# Schematic.net
KiCad netlist of a schematic drawn in EAGLE
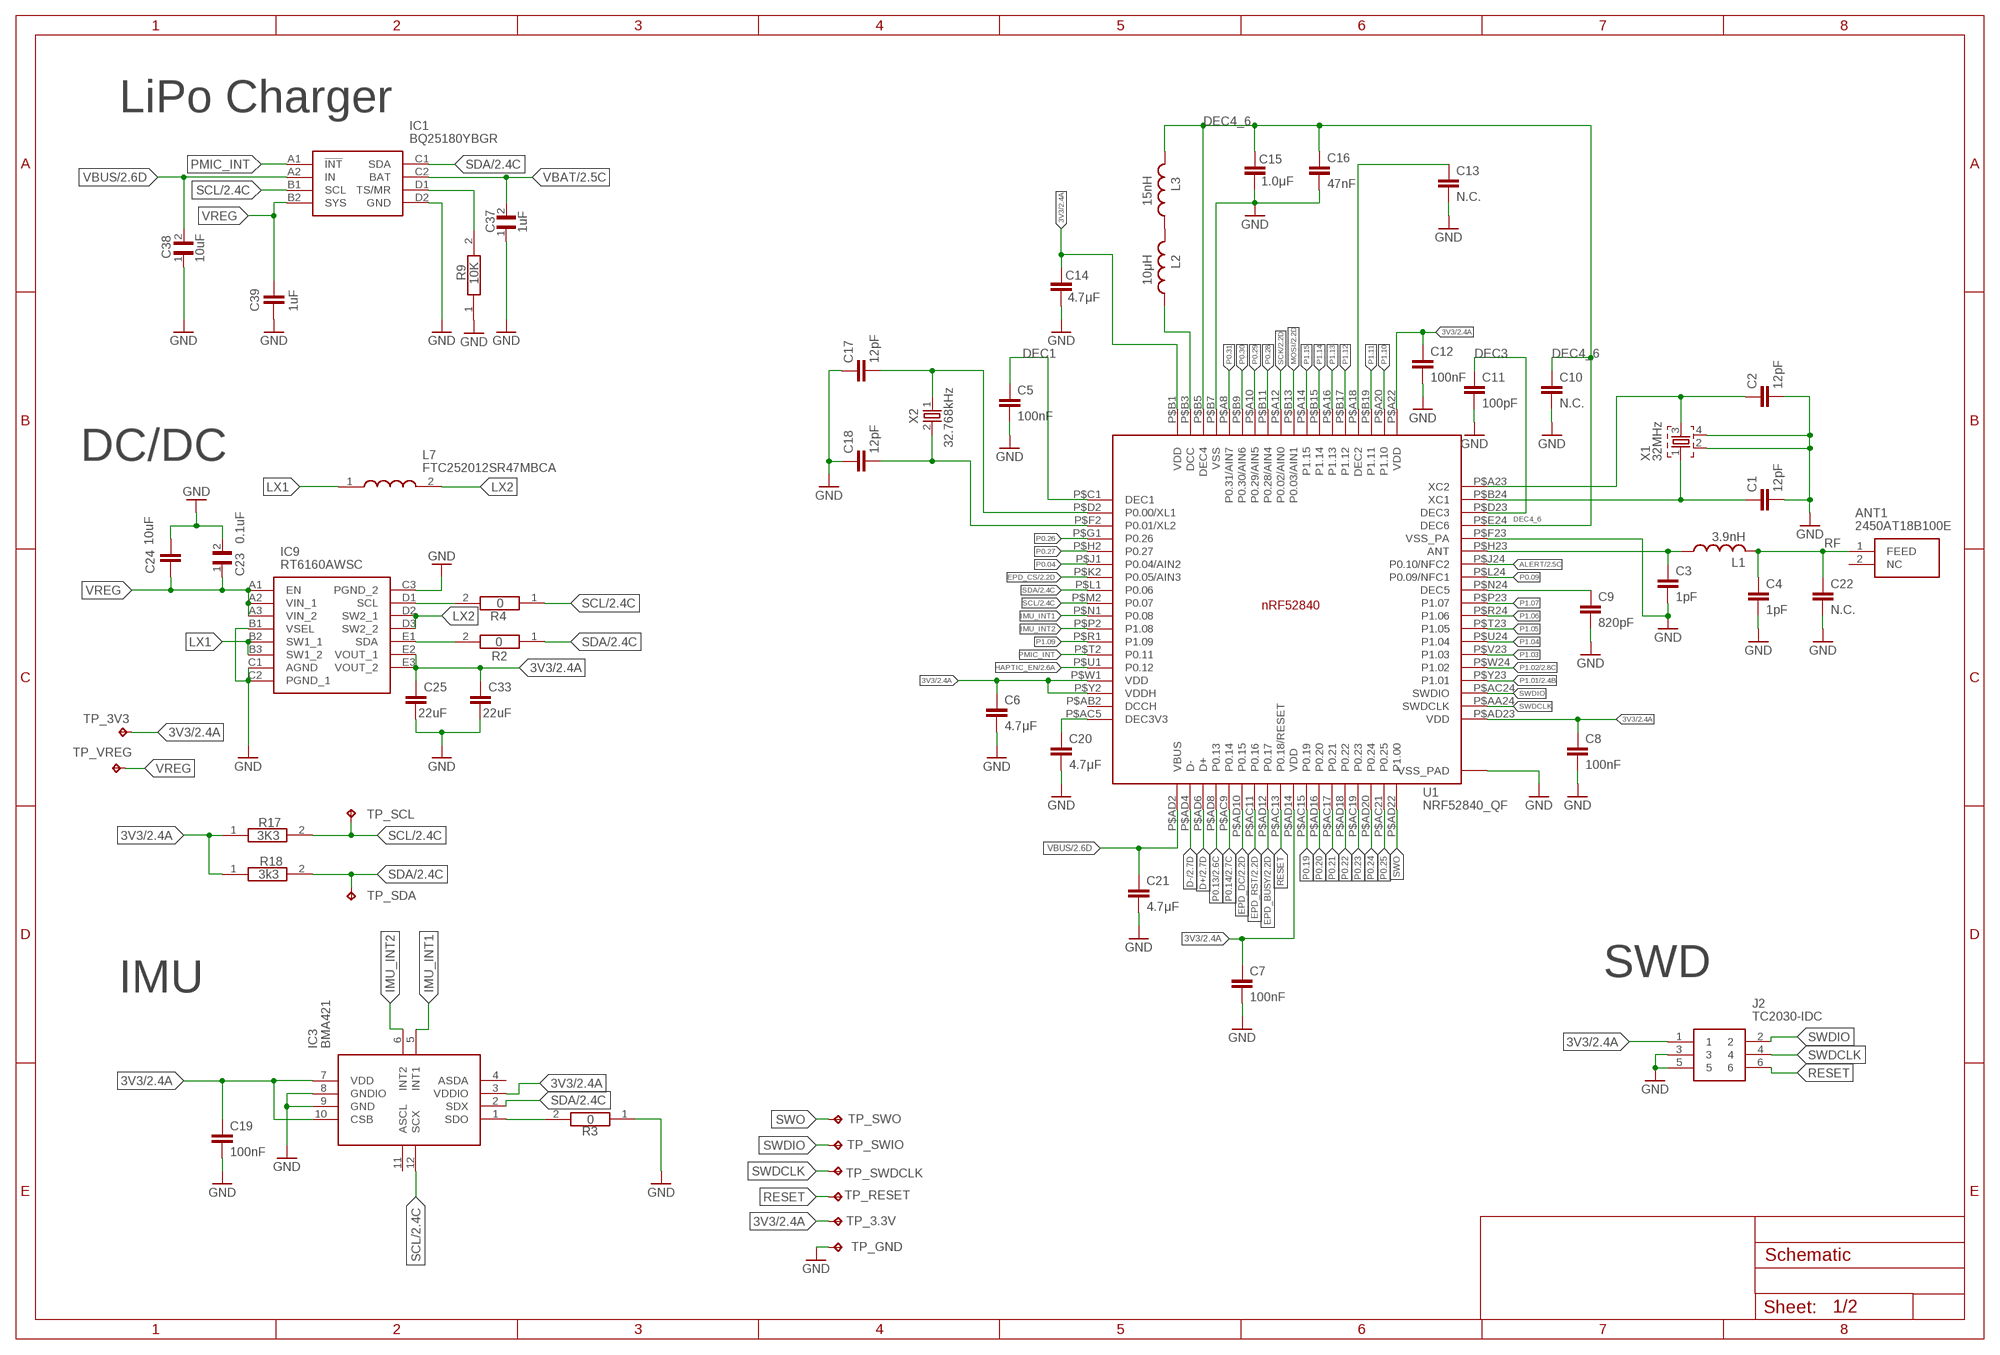
[diagram p0: schematic, sheet 1, part 1 of 2]
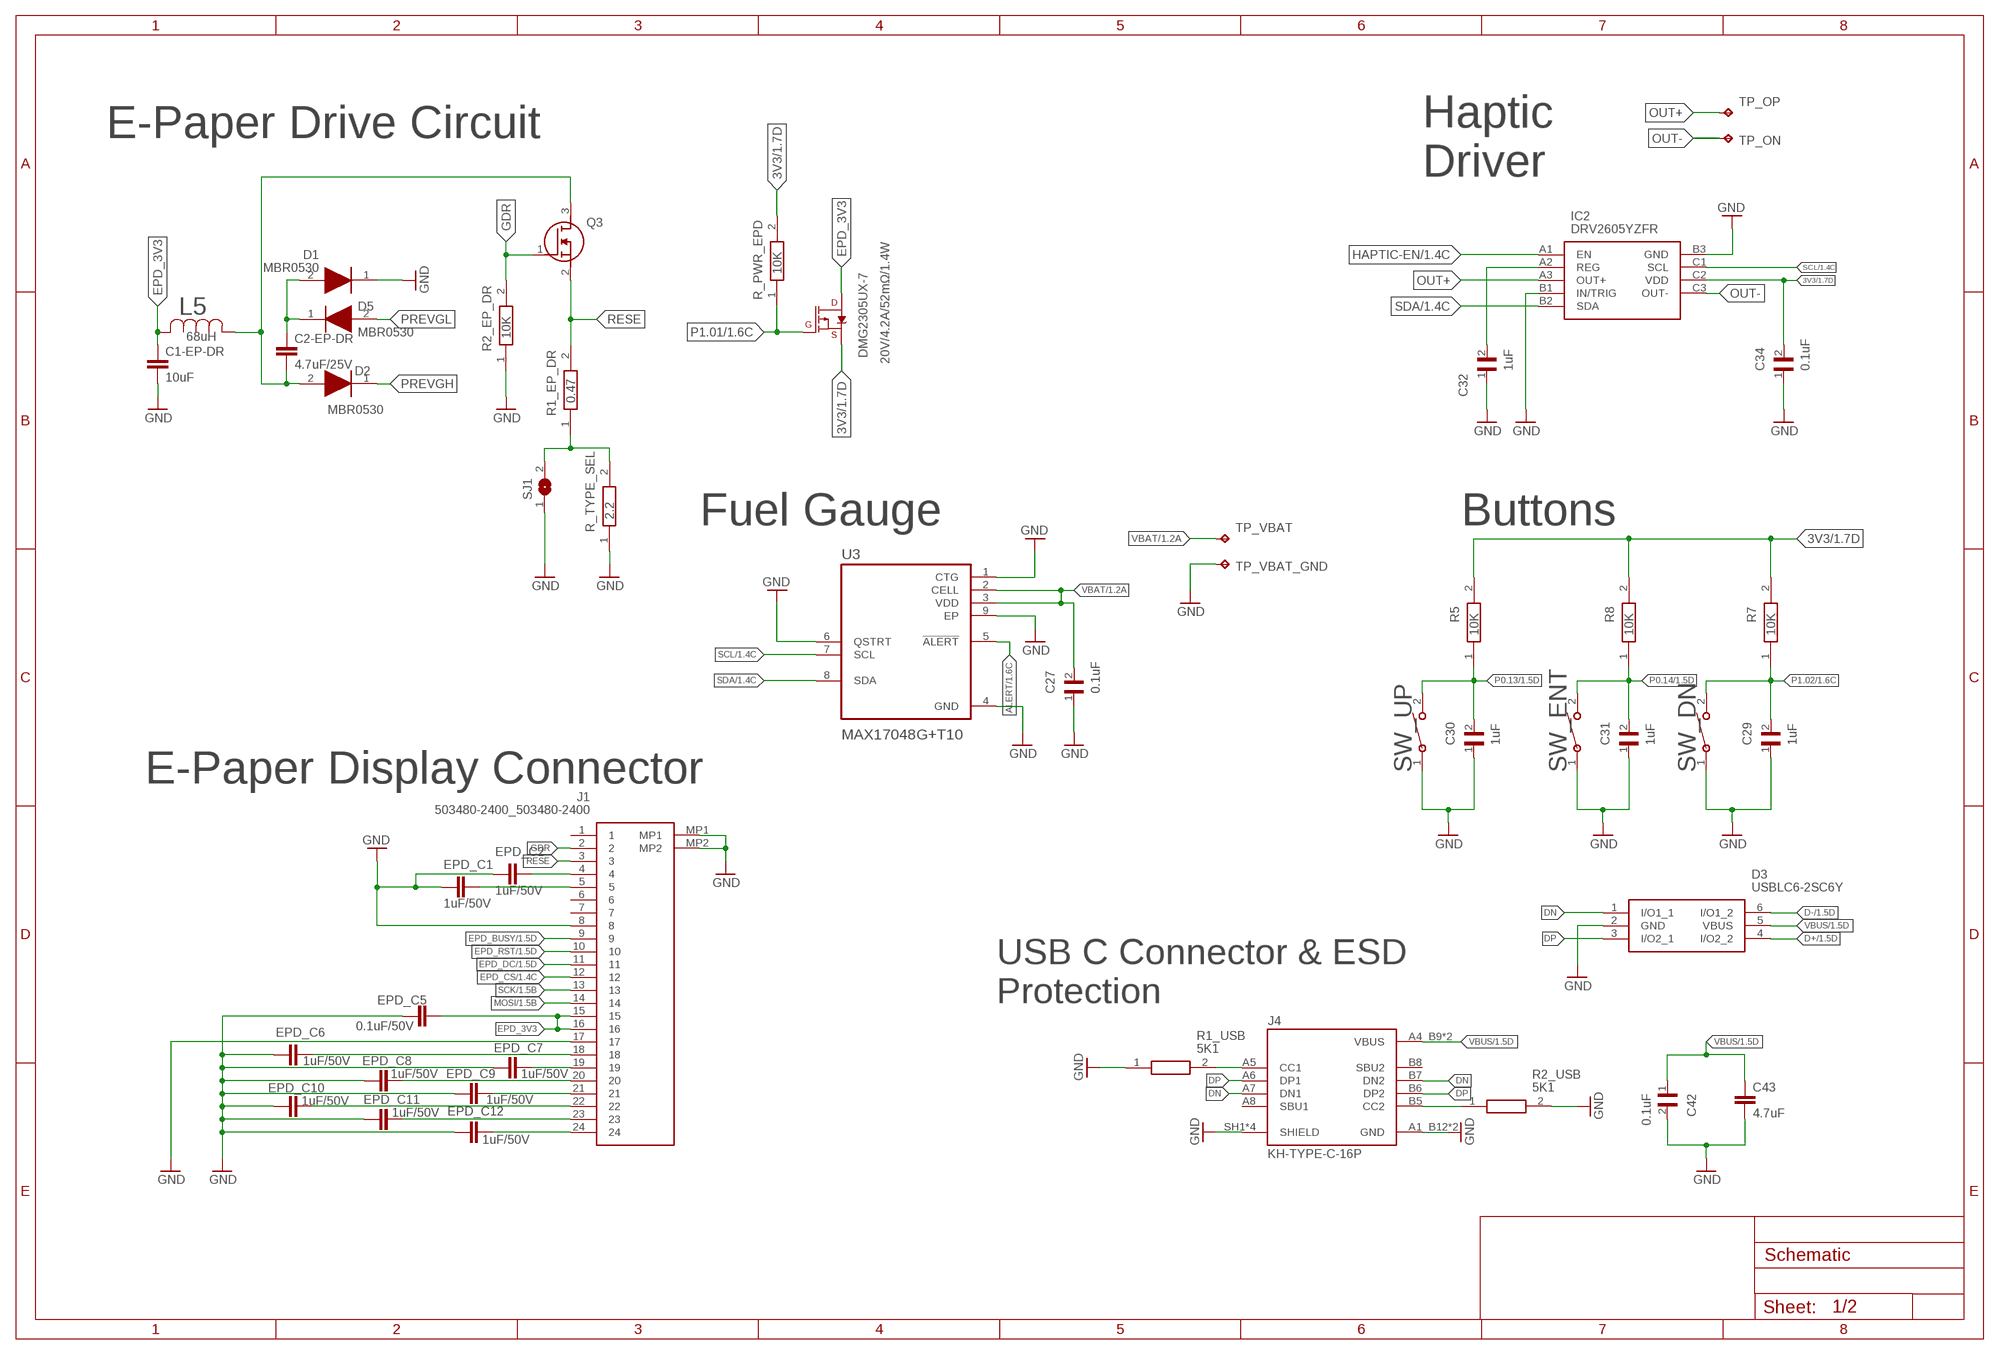
[diagram p1: schematic, sheet 1, part 2 of 2]

(export (version "E")
  (design (tool "Eeschema 10.0.6"))
  (components
    (comp (ref "ANT1")
      (value "2450AT18B100E")
      (footprint "eagle-import:2450AT18B100E_ANTC3216X140N")
      (fields (field (name "MOUSER_PART_NUMBER") "609-2450AT18B100E"))
      (libsource (lib "eagle-import") (part "2450AT18B100E_2450AT18B100E"))
    )
    (comp (ref "C1")
      (value "12pF")
      (footprint "eagle-import:NORDIC_NRF_3_RESC0201_L")
      (libsource (lib "eagle-import") (part "NORDIC_NRF_3_CAPACITOR_0201_L"))
    )
    (comp (ref "C1-EP-DR")
      (value "10uF")
      (footprint "eagle-import:PERFECT_0402_0402")
      (libsource (lib "eagle-import") (part "PERFECT_0402_CAP_0402"))
    )
    (comp (ref "C2")
      (value "12pF")
      (footprint "eagle-import:NORDIC_NRF_3_RESC0201_L")
      (libsource (lib "eagle-import") (part "NORDIC_NRF_3_CAPACITOR_0201_L"))
    )
    (comp (ref "C2-EP-DR")
      (value "4.7uF/25V")
      (footprint "eagle-import:PERFECT_0402_0402")
      (libsource (lib "eagle-import") (part "PERFECT_0402_CAP_0402"))
    )
    (comp (ref "C3")
      (value "1pF")
      (footprint "eagle-import:NORDIC_NRF_3_RESC0201_L")
      (libsource (lib "eagle-import") (part "NORDIC_NRF_3_CAPACITOR_0201_L"))
    )
    (comp (ref "C4")
      (value "1pF")
      (footprint "eagle-import:NORDIC_NRF_3_RESC0201_L")
      (libsource (lib "eagle-import") (part "NORDIC_NRF_3_CAPACITOR_0201_L"))
    )
    (comp (ref "C5")
      (value "100nF")
      (footprint "eagle-import:NORDIC_NRF_3_RESC0201_L")
      (libsource (lib "eagle-import") (part "NORDIC_NRF_3_CAPACITOR_0201_L"))
    )
    (comp (ref "C6")
      (value "4.7μF")
      (footprint "eagle-import:NORDIC_NRF_3_RESC0402_L")
      (libsource (lib "eagle-import") (part "NORDIC_NRF_3_CAPACITOR_0402_L"))
    )
    (comp (ref "C7")
      (value "100nF")
      (footprint "eagle-import:NORDIC_NRF_3_RESC0201_L")
      (libsource (lib "eagle-import") (part "NORDIC_NRF_3_CAPACITOR_0201_L"))
    )
    (comp (ref "C8")
      (value "100nF")
      (footprint "eagle-import:NORDIC_NRF_3_RESC0201_L")
      (libsource (lib "eagle-import") (part "NORDIC_NRF_3_CAPACITOR_0201_L"))
    )
    (comp (ref "C9")
      (value "820pF")
      (footprint "eagle-import:NORDIC_NRF_3_RESC0201_L")
      (libsource (lib "eagle-import") (part "NORDIC_NRF_3_CAPACITOR_0201_L"))
    )
    (comp (ref "C10")
      (value "N.C.")
      (footprint "eagle-import:NORDIC_NRF_3_RESC0201_L")
      (libsource (lib "eagle-import") (part "NORDIC_NRF_3_CAPACITOR_0201_L"))
    )
    (comp (ref "C11")
      (value "100pF")
      (footprint "eagle-import:NORDIC_NRF_3_RESC0201_L")
      (libsource (lib "eagle-import") (part "NORDIC_NRF_3_CAPACITOR_0201_L"))
    )
    (comp (ref "C12")
      (value "100nF")
      (footprint "eagle-import:NORDIC_NRF_3_RESC0201_L")
      (libsource (lib "eagle-import") (part "NORDIC_NRF_3_CAPACITOR_0201_L"))
    )
    (comp (ref "C13")
      (value "N.C.")
      (footprint "eagle-import:NORDIC_NRF_3_RESC0201_L")
      (libsource (lib "eagle-import") (part "NORDIC_NRF_3_CAPACITOR_0201_L"))
    )
    (comp (ref "C14")
      (value "4.7μF")
      (footprint "eagle-import:NORDIC_NRF_3_RESC0402_L")
      (libsource (lib "eagle-import") (part "NORDIC_NRF_3_CAPACITOR_0402_L"))
    )
    (comp (ref "C15")
      (value "1.0μF")
      (footprint "eagle-import:NORDIC_NRF_3_RESC0402_L")
      (libsource (lib "eagle-import") (part "NORDIC_NRF_3_CAPACITOR_0402_L"))
    )
    (comp (ref "C16")
      (value "47nF")
      (footprint "eagle-import:NORDIC_NRF_3_RESC0201_L")
      (libsource (lib "eagle-import") (part "NORDIC_NRF_3_CAPACITOR_0201_L"))
    )
    (comp (ref "C17")
      (value "12pF")
      (footprint "eagle-import:NORDIC_NRF_3_RESC0201_L")
      (libsource (lib "eagle-import") (part "NORDIC_NRF_3_CAPACITOR_0201_L"))
    )
    (comp (ref "C18")
      (value "12pF")
      (footprint "eagle-import:NORDIC_NRF_3_RESC0201_L")
      (libsource (lib "eagle-import") (part "NORDIC_NRF_3_CAPACITOR_0201_L"))
    )
    (comp (ref "C19")
      (value "100nF")
      (footprint "eagle-import:NORDIC_NRF_3_RESC0201_L")
      (libsource (lib "eagle-import") (part "NORDIC_NRF_3_CAPACITOR_0201_L"))
    )
    (comp (ref "C20")
      (value "4.7μF")
      (footprint "eagle-import:NORDIC_NRF_3_RESC0402_L")
      (libsource (lib "eagle-import") (part "NORDIC_NRF_3_CAPACITOR_0402_L"))
    )
    (comp (ref "C21")
      (value "4.7μF")
      (footprint "eagle-import:NORDIC_NRF_3_RESC0402_L")
      (libsource (lib "eagle-import") (part "NORDIC_NRF_3_CAPACITOR_0402_L"))
    )
    (comp (ref "C22")
      (value "N.C.")
      (footprint "eagle-import:NORDIC_NRF_3_RESC0201_L")
      (libsource (lib "eagle-import") (part "NORDIC_NRF_3_CAPACITOR_0201_L"))
    )
    (comp (ref "C23")
      (value "0.1uF")
      (footprint "eagle-import:GRM011R60J152KE01L_2_CAPC0201X13N")
      (fields (field (name "MF") "Murata") (field (name "MP") "GRM011R60J152KE01L"))
      (libsource (lib "eagle-import") (part "GRM011R60J152KE01L_2_GRM011R60J152KE01L"))
    )
    (comp (ref "C24")
      (value "10uF")
      (footprint "eagle-import:NORDIC_NRF_3_RESC0402_L")
      (libsource (lib "eagle-import") (part "NORDIC_NRF_3_CAPACITOR_0402_L"))
    )
    (comp (ref "C25")
      (value "22uF")
      (footprint "eagle-import:NORDIC_NRF_3_RESC0402_L")
      (libsource (lib "eagle-import") (part "NORDIC_NRF_3_CAPACITOR_0402_L"))
    )
    (comp (ref "C27")
      (value "0.1uF")
      (footprint "eagle-import:GRM011R60J152KE01L_2_CAPC0201X13N")
      (fields (field (name "MF") "Murata") (field (name "MP") "GRM011R60J152KE01L"))
      (libsource (lib "eagle-import") (part "GRM011R60J152KE01L_2_GRM011R60J152KE01L"))
    )
    (comp (ref "C29")
      (value "1uF")
      (footprint "eagle-import:GRM011R60J152KE01L_2_CAPC0201X13N")
      (fields (field (name "MF") "Murata") (field (name "MP") "GRM011R60J152KE01L"))
      (libsource (lib "eagle-import") (part "GRM011R60J152KE01L_2_GRM011R60J152KE01L"))
    )
    (comp (ref "C30")
      (value "1uF")
      (footprint "eagle-import:GRM011R60J152KE01L_2_CAPC0201X13N")
      (fields (field (name "MF") "Murata") (field (name "MP") "GRM011R60J152KE01L"))
      (libsource (lib "eagle-import") (part "GRM011R60J152KE01L_2_GRM011R60J152KE01L"))
    )
    (comp (ref "C31")
      (value "1uF")
      (footprint "eagle-import:GRM011R60J152KE01L_2_CAPC0201X13N")
      (fields (field (name "MF") "Murata") (field (name "MP") "GRM011R60J152KE01L"))
      (libsource (lib "eagle-import") (part "GRM011R60J152KE01L_2_GRM011R60J152KE01L"))
    )
    (comp (ref "C32")
      (value "1uF")
      (footprint "eagle-import:GRM011R60J152KE01L_2_CAPC0201X13N")
      (fields (field (name "MF") "Murata") (field (name "MP") "GRM011R60J152KE01L"))
      (libsource (lib "eagle-import") (part "GRM011R60J152KE01L_2_GRM011R60J152KE01L"))
    )
    (comp (ref "C33")
      (value "22uF")
      (footprint "eagle-import:NORDIC_NRF_3_RESC0402_L")
      (libsource (lib "eagle-import") (part "NORDIC_NRF_3_CAPACITOR_0402_L"))
    )
    (comp (ref "C34")
      (value "0.1uF")
      (footprint "eagle-import:GRM011R60J152KE01L_2_CAPC0201X13N")
      (fields (field (name "MF") "Murata") (field (name "MP") "GRM011R60J152KE01L"))
      (libsource (lib "eagle-import") (part "GRM011R60J152KE01L_2_GRM011R60J152KE01L"))
    )
    (comp (ref "C37")
      (value "1uF")
      (footprint "eagle-import:GRM011R60J152KE01L_2_CAPC0201X13N")
      (fields (field (name "MF") "Murata") (field (name "MP") "GRM011R60J152KE01L"))
      (libsource (lib "eagle-import") (part "GRM011R60J152KE01L_2_GRM011R60J152KE01L"))
    )
    (comp (ref "C38")
      (value "10uF")
      (footprint "eagle-import:GRM011R60J152KE01L_2_CAPC0201X13N")
      (fields (field (name "MF") "Murata") (field (name "MP") "GRM011R60J152KE01L"))
      (libsource (lib "eagle-import") (part "GRM011R60J152KE01L_2_GRM011R60J152KE01L"))
    )
    (comp (ref "C39")
      (value "1uF")
      (footprint "eagle-import:NORDIC_NRF_3_RESC0402_L")
      (libsource (lib "eagle-import") (part "NORDIC_NRF_3_CAPACITOR_0402_L"))
    )
    (comp (ref "C42")
      (value "0.1uF")
      (footprint "eagle-import:GRM011R60J152KE01L_2_CAPC0201X13N")
      (fields (field (name "MF") "Murata") (field (name "MP") "GRM011R60J152KE01L"))
      (libsource (lib "eagle-import") (part "GRM011R60J152KE01L_2_GRM011R60J152KE01L"))
    )
    (comp (ref "C43")
      (value "4.7uF")
      (footprint "eagle-import:PERFECT_0402_0402")
      (libsource (lib "eagle-import") (part "PERFECT_0402_CAP_0402"))
    )
    (comp (ref "D1")
      (value "MBR0530")
      (footprint "eagle-import:ESP32_C6_LIBRARY_5_SOD3716X135N")
      (fields (field (name "MF") "ON Semiconductor"))
      (libsource (lib "eagle-import") (part "ESP32_C6_LIBRARY_5_MBR0530"))
    )
    (comp (ref "D2")
      (value "MBR0530")
      (footprint "eagle-import:ESP32_C6_LIBRARY_5_SOD3716X135N")
      (fields (field (name "MF") "ON Semiconductor"))
      (libsource (lib "eagle-import") (part "ESP32_C6_LIBRARY_5_MBR0530"))
    )
    (comp (ref "D3")
      (value "USBLC6-2SC6Y")
      (footprint "eagle-import:ESP32_C6_LIBRARY_3_SOT95P280X145-6N")
      (fields (field (name "MF") "STMicroelectronics"))
      (libsource (lib "eagle-import") (part "ESP32_C6_LIBRARY_3_USBLC6-2SC6Y"))
    )
    (comp (ref "D5")
      (value "MBR0530")
      (footprint "eagle-import:ESP32_C6_LIBRARY_5_SOD3716X135N")
      (fields (field (name "MF") "ON Semiconductor"))
      (libsource (lib "eagle-import") (part "ESP32_C6_LIBRARY_5_MBR0530"))
    )
    (comp (ref "DMG2305UX-7")
      (value "20V/4.2A/52mΩ/1.4W")
      (footprint "eagle-import:ESP32_C6_LIBRARY_4_ESP32_C6_LIBRARY_4_ESP32_C6_LIBRARY_4_ESP32_C6_LIBRARY_4_ESP32_WROVER_SPARKFUN-DISCRETESEMI_SOT23-3")
      (libsource (lib "eagle-import") (part "ESP32_C6_LIBRARY_4_ESP32_WROVER_SPARKFUN-DISCRETESEMI_MOSFET_PCH-DMG2305UX-7"))
    )
    (comp (ref "EPD_C1")
      (value "1uF/50V")
      (footprint "eagle-import:PERFECT_0402_0402")
      (libsource (lib "eagle-import") (part "PERFECT_0402_CAP_0402"))
    )
    (comp (ref "EPD_C2")
      (value "1uF/50V")
      (footprint "eagle-import:PERFECT_0402_0402")
      (libsource (lib "eagle-import") (part "PERFECT_0402_CAP_0402"))
    )
    (comp (ref "EPD_C5")
      (value "0.1uF/50V")
      (footprint "eagle-import:NORDIC_NRF_3_RESC0201_L")
      (libsource (lib "eagle-import") (part "Library_proiect_vf.6mj5mWEzRZml-z0rj9qWig_NORDIC_NRF_3_CAPACITOR_0201_L"))
    )
    (comp (ref "EPD_C6")
      (value "1uF/50V")
      (footprint "eagle-import:PERFECT_0402_0402")
      (libsource (lib "eagle-import") (part "PERFECT_0402_CAP_0402"))
    )
    (comp (ref "EPD_C7")
      (value "1uF/50V")
      (footprint "eagle-import:PERFECT_0402_0402")
      (libsource (lib "eagle-import") (part "PERFECT_0402_CAP_0402"))
    )
    (comp (ref "EPD_C8")
      (value "1uF/50V")
      (footprint "eagle-import:PERFECT_0402_0402")
      (libsource (lib "eagle-import") (part "PERFECT_0402_CAP_0402"))
    )
    (comp (ref "EPD_C9")
      (value "1uF/50V")
      (footprint "eagle-import:PERFECT_0402_0402")
      (libsource (lib "eagle-import") (part "PERFECT_0402_CAP_0402"))
    )
    (comp (ref "EPD_C10")
      (value "1uF/50V")
      (footprint "eagle-import:PERFECT_0402_0402")
      (libsource (lib "eagle-import") (part "PERFECT_0402_CAP_0402"))
    )
    (comp (ref "EPD_C11")
      (value "1uF/50V")
      (footprint "eagle-import:PERFECT_0402_0402")
      (libsource (lib "eagle-import") (part "PERFECT_0402_CAP_0402"))
    )
    (comp (ref "EPD_C12")
      (value "1uF/50V")
      (footprint "eagle-import:PERFECT_0402_0402")
      (libsource (lib "eagle-import") (part "PERFECT_0402_CAP_0402"))
    )
    (comp (ref "IC1")
      (value "BQ25180YBGR")
      (footprint "eagle-import:BQ25180YBGR_BGA8C40P2X4_100X155X50")
      (fields (field (name "MOUSER_PART_NUMBER") "595-BQ25180YBGR"))
      (libsource (lib "eagle-import") (part "BQ25180YBGR_BQ25180YBGR"))
    )
    (comp (ref "IC2")
      (value "DRV2605YZFR")
      (footprint "eagle-import:DRV2605YZFR_BGA9C50P3X3_144X144X62")
      (libsource (lib "eagle-import") (part "DRV2605YZFR_DRV2605YZFR"))
    )
    (comp (ref "IC3")
      (value "BMA421")
      (footprint "eagle-import:BMA423_BMA423")
      (fields (field (name "ARROW_PART_NUMBER") "BMA423") (field (name "MOUSER_PART_NUMBER") "262-BMA423"))
      (libsource (lib "eagle-import") (part "BMA423_BMA423"))
    )
    (comp (ref "IC9")
      (value "RT6160AWSC")
      (footprint "eagle-import:RT6160AWSC_BGA15C40P3X5_140X230X60")
      (fields (field (name "MOUSER_PART_NUMBER") "835-RT6160AWSC"))
      (libsource (lib "eagle-import") (part "RT6160AWSC_RT6160AWSC"))
    )
    (comp (ref "J1")
      (value "503480-2400_503480-2400")
      (footprint "eagle-import:503480-2400_5034802400")
      (fields
        (field (name "MANUFACTURER_PART_NUMBER") "503480-2400")
        (field (name "MOUSER_PART_NUMBER") "538-503480-2400")
      )
      (libsource (lib "eagle-import") (part "503480-2400_503480-2400"))
    )
    (comp (ref "J2")
      (value "TC2030-IDC")
      (footprint "eagle-import:TC2030-IDC_TC2030IDC")
      (libsource (lib "eagle-import") (part "TC2030-IDC_TC2030-IDC"))
    )
    (comp (ref "J4")
      (value "KH-TYPE-C-16P")
      (footprint "eagle-import:KH-TYPE-C-16P_KINGHELM_KH-TYPE-C-16P")
      (fields (field (name "MF") "kinghelm"))
      (libsource (lib "eagle-import") (part "KH-TYPE-C-16P_KH-TYPE-C-16P"))
    )
    (comp (ref "L1")
      (value "3.9nH")
      (footprint "eagle-import:NORDIC_NRF_2_RESC0402_L")
      (libsource (lib "eagle-import") (part "NORDIC_NRF_2_INDUCTOR_0402_L"))
    )
    (comp (ref "L2")
      (value "10μH")
      (footprint "eagle-import:NORDIC_NRF_2_RESC0402_L")
      (libsource (lib "eagle-import") (part "NORDIC_NRF_2_INDUCTOR_0402_L"))
    )
    (comp (ref "L3")
      (value "15nH")
      (footprint "eagle-import:NORDIC_NRF_2_RESC0402_L")
      (libsource (lib "eagle-import") (part "NORDIC_NRF_2_INDUCTOR_0402_L"))
    )
    (comp (ref "L5")
      (value "68uH")
      (footprint "eagle-import:ESP32_C6_LIBRARY_2_IND_4828-WE-TPC_WRE")
      (fields
        (field (name "MANUFACTURER_PART_NUMBER") "744043680")
        (field (name "COPYRIGHT") "Copyright (C) 2024 Ultra Librarian. All rights reserved.")
      )
      (libsource (lib "eagle-import") (part "ESP32_C6_LIBRARY_2_744043680IND_4828-WE-TPC_WRE"))
    )
    (comp (ref "L7")
      (value "FTC252012SR47MBCA")
      (footprint "eagle-import:MLP2016SR47MT0S1_INDC2016X100N")
      (libsource (lib "eagle-import") (part "MLP2016SR47MT0S1_FTC252012SR47MBCA"))
    )
    (comp (ref "Q3")
      (value "SI1308EDL-T1-GE3")
      (footprint "eagle-import:ESP32_C6_LIBRARY_6_SOT65P210X110-3N")
      (fields (field (name "MF") "Vishay Siliconix"))
      (libsource (lib "eagle-import") (part "ESP32_C6_LIBRARY_6_SI1308EDL-T1-GE3"))
    )
    (comp (ref "R1_EP_DR")
      (value "0.47")
      (footprint "eagle-import:CPF0201D7K68C1_0201")
      (libsource (lib "eagle-import") (part "Library_proiect_vf.6mj5mWEzRZml-z0rj9qWig_CPF0201D7K68C1_CPF0201D7K68C1"))
    )
    (comp (ref "R1_USB")
      (value "5K1")
      (footprint "eagle-import:CPF0201D7K68C1_0201")
      (libsource (lib "eagle-import") (part "Library_proiect_vf.6mj5mWEzRZml-z0rj9qWig_CPF0201D7K68C1_CPF0201D7K68C1"))
    )
    (comp (ref "R2")
      (value "0")
      (footprint "eagle-import:CPF0201D7K68C1_0201")
      (libsource (lib "eagle-import") (part "CPF0201D7K68C1_CPF0201D7K68C1"))
    )
    (comp (ref "R2_EP_DR")
      (value "10K")
      (footprint "eagle-import:CPF0201D7K68C1_0201")
      (libsource (lib "eagle-import") (part "Library_proiect_vf.6mj5mWEzRZml-z0rj9qWig_CPF0201D7K68C1_CPF0201D7K68C1"))
    )
    (comp (ref "R2_USB")
      (value "5K1")
      (footprint "eagle-import:CPF0201D7K68C1_0201")
      (libsource (lib "eagle-import") (part "Library_proiect_vf.6mj5mWEzRZml-z0rj9qWig_CPF0201D7K68C1_CPF0201D7K68C1"))
    )
    (comp (ref "R3")
      (value "0")
      (footprint "eagle-import:CPF0201D7K68C1_0201")
      (libsource (lib "eagle-import") (part "CPF0201D7K68C1_CPF0201D7K68C1"))
    )
    (comp (ref "R4")
      (value "0")
      (footprint "eagle-import:CPF0201D7K68C1_0201")
      (libsource (lib "eagle-import") (part "CPF0201D7K68C1_CPF0201D7K68C1"))
    )
    (comp (ref "R5")
      (value "10K")
      (footprint "eagle-import:CPF0201D7K68C1_0201")
      (libsource (lib "eagle-import") (part "Library_proiect_vf.6mj5mWEzRZml-z0rj9qWig_CPF0201D7K68C1_CPF0201D7K68C1"))
    )
    (comp (ref "R7")
      (value "10K")
      (footprint "eagle-import:CPF0201D7K68C1_0201")
      (libsource (lib "eagle-import") (part "Library_proiect_vf.6mj5mWEzRZml-z0rj9qWig_CPF0201D7K68C1_CPF0201D7K68C1"))
    )
    (comp (ref "R8")
      (value "10K")
      (footprint "eagle-import:CPF0201D7K68C1_0201")
      (libsource (lib "eagle-import") (part "Library_proiect_vf.6mj5mWEzRZml-z0rj9qWig_CPF0201D7K68C1_CPF0201D7K68C1"))
    )
    (comp (ref "R9")
      (value "10K")
      (footprint "eagle-import:CPF0201D7K68C1_0201")
      (libsource (lib "eagle-import") (part "CPF0201D7K68C1_CPF0201D7K68C1"))
    )
    (comp (ref "R17")
      (value "3K3")
      (footprint "eagle-import:ERA-1AEB3401C_0201")
      (libsource (lib "eagle-import") (part "ERA-1AEB3401C_CPF0201D7K68C1"))
    )
    (comp (ref "R18")
      (value "3k3")
      (footprint "eagle-import:ERA-1AEB3401C_0201")
      (libsource (lib "eagle-import") (part "ERA-1AEB3401C_CPF0201D7K68C1"))
    )
    (comp (ref "R_PWR_EPD")
      (value "10K")
      (footprint "eagle-import:CPF0201D7K68C1_0201")
      (libsource (lib "eagle-import") (part "Library_proiect_vf.6mj5mWEzRZml-z0rj9qWig_CPF0201D7K68C1_CPF0201D7K68C1"))
    )
    (comp (ref "R_TYPE_SEL")
      (value "2.2")
      (footprint "eagle-import:CPF0201D7K68C1_0201")
      (libsource (lib "eagle-import") (part "Library_proiect_vf.6mj5mWEzRZml-z0rj9qWig_CPF0201D7K68C1_CPF0201D7K68C1"))
    )
    (comp (ref "SJ1")
      (value "ESP32_C6_LIBRARY_7_JUMPER_SJ")
      (footprint "eagle-import:ESP32_C6_LIBRARY_7_JUMPER_SJ")
      (libsource (lib "eagle-import") (part "ESP32_C6_LIBRARY_7_JUMPER_SJ"))
    )
    (comp (ref "SW_DN")
      (value "2025-10-22_07-23-44_LIBRARY_EVP-AKE31ASW_EVP-AKE31A_PAN")
      (footprint "eagle-import:2025-10-22_07-23-44_LIBRARY_SW_EVP-AKE31A_PAN")
      (fields
        (field (name "MANUFACTURER_PART_NUMBER") "EVP-AKE31A")
        (field (name "COPYRIGHT") "Copyright (C) 2025 Ultra Librarian. All rights reserved.")
      )
      (libsource (lib "eagle-import") (part "2025-10-22_07-23-44_LIBRARY_EVP-AKE31ASW_EVP-AKE31A_PAN"))
    )
    (comp (ref "SW_ENT")
      (value "2025-10-22_07-23-44_LIBRARY_EVP-AKE31ASW_EVP-AKE31A_PAN")
      (footprint "eagle-import:2025-10-22_07-23-44_LIBRARY_SW_EVP-AKE31A_PAN")
      (fields
        (field (name "MANUFACTURER_PART_NUMBER") "EVP-AKE31A")
        (field (name "COPYRIGHT") "Copyright (C) 2025 Ultra Librarian. All rights reserved.")
      )
      (libsource (lib "eagle-import") (part "2025-10-22_07-23-44_LIBRARY_EVP-AKE31ASW_EVP-AKE31A_PAN"))
    )
    (comp (ref "SW_UP")
      (value "2025-10-22_07-23-44_LIBRARY_EVP-AKE31ASW_EVP-AKE31A_PAN")
      (footprint "eagle-import:2025-10-22_07-23-44_LIBRARY_SW_EVP-AKE31A_PAN")
      (fields
        (field (name "MANUFACTURER_PART_NUMBER") "EVP-AKE31A")
        (field (name "COPYRIGHT") "Copyright (C) 2025 Ultra Librarian. All rights reserved.")
      )
      (libsource (lib "eagle-import") (part "2025-10-22_07-23-44_LIBRARY_EVP-AKE31ASW_EVP-AKE31A_PAN"))
    )
    (comp (ref "TP_3.3V")
      (value "HECTOR_WATCH_1_TPTP20R")
      (footprint "eagle-import:HECTOR_WATCH_1_TP20R")
      (libsource (lib "eagle-import") (part "HECTOR_WATCH_1_TPTP20R"))
    )
    (comp (ref "TP_3V3")
      (value "HECTOR_WATCH_1_TPTP20R")
      (footprint "eagle-import:HECTOR_WATCH_1_TP20R")
      (libsource (lib "eagle-import") (part "HECTOR_WATCH_1_TPTP20R"))
    )
    (comp (ref "TP_GND")
      (value "HECTOR_WATCH_1_TPTP20R")
      (footprint "eagle-import:HECTOR_WATCH_1_TP20R")
      (libsource (lib "eagle-import") (part "HECTOR_WATCH_1_TPTP20R"))
    )
    (comp (ref "TP_ON")
      (value "HECTOR_WATCH_1_TPTP20R")
      (footprint "eagle-import:HECTOR_WATCH_1_TP20R")
      (libsource (lib "eagle-import") (part "Library_proiect_vf.6mj5mWEzRZml-z0rj9qWig_HECTOR_WATCH_1_TPTP20R"))
    )
    (comp (ref "TP_OP")
      (value "HECTOR_WATCH_1_TPTP20R")
      (footprint "eagle-import:HECTOR_WATCH_1_TP20R")
      (libsource (lib "eagle-import") (part "Library_proiect_vf.6mj5mWEzRZml-z0rj9qWig_HECTOR_WATCH_1_TPTP20R"))
    )
    (comp (ref "TP_RESET")
      (value "HECTOR_WATCH_1_TPTP20R")
      (footprint "eagle-import:HECTOR_WATCH_1_TP20R")
      (libsource (lib "eagle-import") (part "HECTOR_WATCH_1_TPTP20R"))
    )
    (comp (ref "TP_SCL")
      (value "HECTOR_WATCH_1_TPTP20R")
      (footprint "eagle-import:HECTOR_WATCH_1_TP20R")
      (libsource (lib "eagle-import") (part "HECTOR_WATCH_1_TPTP20R"))
    )
    (comp (ref "TP_SDA")
      (value "HECTOR_WATCH_1_TPTP20R")
      (footprint "eagle-import:HECTOR_WATCH_1_TP20R")
      (libsource (lib "eagle-import") (part "HECTOR_WATCH_1_TPTP20R"))
    )
    (comp (ref "TP_SWDCLK")
      (value "HECTOR_WATCH_1_TPTP20R")
      (footprint "eagle-import:HECTOR_WATCH_1_TP20R")
      (libsource (lib "eagle-import") (part "HECTOR_WATCH_1_TPTP20R"))
    )
    (comp (ref "TP_SWIO")
      (value "HECTOR_WATCH_1_TPTP20R")
      (footprint "eagle-import:HECTOR_WATCH_1_TP20R")
      (libsource (lib "eagle-import") (part "HECTOR_WATCH_1_TPTP20R"))
    )
    (comp (ref "TP_SWO")
      (value "HECTOR_WATCH_1_TPTP20R")
      (footprint "eagle-import:HECTOR_WATCH_1_TP20R")
      (libsource (lib "eagle-import") (part "HECTOR_WATCH_1_TPTP20R"))
    )
    (comp (ref "TP_VBAT")
      (value "HECTOR_WATCH_1_TPTP20R")
      (footprint "eagle-import:HECTOR_WATCH_1_TP20R")
      (libsource (lib "eagle-import") (part "Library_proiect_vf.6mj5mWEzRZml-z0rj9qWig_HECTOR_WATCH_1_TPTP20R"))
    )
    (comp (ref "TP_VBAT_GND")
      (value "HECTOR_WATCH_1_TPTP20R")
      (footprint "eagle-import:HECTOR_WATCH_1_TP20R")
      (libsource (lib "eagle-import") (part "Library_proiect_vf.6mj5mWEzRZml-z0rj9qWig_HECTOR_WATCH_1_TPTP20R"))
    )
    (comp (ref "TP_VREG")
      (value "HECTOR_WATCH_1_TPTP20R")
      (footprint "eagle-import:HECTOR_WATCH_1_TP20R")
      (libsource (lib "eagle-import") (part "HECTOR_WATCH_1_TPTP20R"))
    )
    (comp (ref "U1")
      (value "NRF52840_QF")
      (footprint "eagle-import:NORDIC_NRF_4_AQFN50P700X700X85_HS-74N")
      (libsource (lib "eagle-import") (part "NORDIC_NRF_4_NRF52840_QF"))
    )
    (comp (ref "U3")
      (value "MAX17048G+T10")
      (footprint "eagle-import:ESP32_C6_LIBRARY_SON50P200X200X80-9N")
      (fields (field (name "MF") "Analog Devices"))
      (libsource (lib "eagle-import") (part "ESP32_C6_LIBRARY_MAX17048G+T10"))
    )
    (comp (ref "X1")
      (value "32MHz")
      (footprint "eagle-import:NORDIC_NRF_BT-XTAL_2016_N")
      (libsource (lib "eagle-import") (part "NORDIC_NRF_XTAL_32MHZ"))
    )
    (comp (ref "X2")
      (value "32.768kHz")
      (footprint "eagle-import:NORDIC_NRF_1_XTAL_3215_N")
      (libsource (lib "eagle-import") (part "NORDIC_NRF_1_XTAL_32KHZ"))
    )
  )
  (nets
    (net (code "1") (name "3V3{slash}1.7D") (class "Default")
      (node (ref "C34") (pin "2") (pinfunction "2_2") (pintype "passive"))
      (node (ref "DMG2305UX-7") (pin "2") (pinfunction "S_2") (pintype "bidirectional"))
      (node (ref "IC2") (pin "C2") (pinfunction "VDD_C2") (pintype "bidirectional"))
      (node (ref "R5") (pin "2") (pinfunction "2_2") (pintype "bidirectional"))
      (node (ref "R7") (pin "2") (pinfunction "2_2") (pintype "bidirectional"))
      (node (ref "R8") (pin "2") (pinfunction "2_2") (pintype "bidirectional"))
      (node (ref "R_PWR_EPD") (pin "2") (pinfunction "2_2") (pintype "bidirectional"))
    )
    (net (code "2") (name "3V3{slash}2.4A") (class "Default")
      (node (ref "C12") (pin "1") (pinfunction "1_1") (pintype "passive"))
      (node (ref "C14") (pin "1") (pinfunction "1_1") (pintype "passive"))
      (node (ref "C19") (pin "1") (pinfunction "1_1") (pintype "passive"))
      (node (ref "C25") (pin "1") (pinfunction "1_1") (pintype "passive"))
      (node (ref "C33") (pin "1") (pinfunction "1_1") (pintype "passive"))
      (node (ref "C6") (pin "1") (pinfunction "1_1") (pintype "passive"))
      (node (ref "C7") (pin "1") (pinfunction "1_1") (pintype "passive"))
      (node (ref "C8") (pin "1") (pinfunction "1_1") (pintype "passive"))
      (node (ref "IC3") (pin "10") (pinfunction "CSB_10") (pintype "bidirectional"))
      (node (ref "IC3") (pin "3") (pinfunction "VDDIO_3") (pintype "bidirectional"))
      (node (ref "IC3") (pin "7") (pinfunction "VDD_7") (pintype "bidirectional"))
      (node (ref "IC9") (pin "E2") (pinfunction "VOUT_1_E2") (pintype "bidirectional"))
      (node (ref "IC9") (pin "E3") (pinfunction "VOUT_2_E3") (pintype "bidirectional"))
      (node (ref "J2") (pin "1") (pinfunction "1_1") (pintype "bidirectional"))
      (node (ref "R17") (pin "1") (pinfunction "1_1") (pintype "bidirectional"))
      (node (ref "R18") (pin "1") (pinfunction "1_1") (pintype "bidirectional"))
      (node (ref "TP_3.3V") (pin "TP") (pinfunction "TP_TP") (pintype "input"))
      (node (ref "TP_3V3") (pin "TP") (pinfunction "TP_TP") (pintype "input"))
      (node (ref "U1") (pin "P$A22") (pinfunction "VDD_P$A22") (pintype "power_in"))
      (node (ref "U1") (pin "P$AD14") (pinfunction "VDD_P$AD14") (pintype "power_in"))
      (node (ref "U1") (pin "P$AD23") (pinfunction "VDD_P$AD23") (pintype "power_in"))
      (node (ref "U1") (pin "P$B1") (pinfunction "VDD_P$B1") (pintype "power_in"))
      (node (ref "U1") (pin "P$W1") (pinfunction "VDD_P$W1") (pintype "power_in"))
      (node (ref "U1") (pin "P$Y2") (pinfunction "VDDH_P$Y2") (pintype "power_in"))
    )
    (net (code "3") (name "ALERT{slash}1.6C") (class "Default")
      (node (ref "U3") (pin "5") (pinfunction "~{ALERT}_5") (pintype "output"))
    )
    (net (code "4") (name "ALERT{slash}2.5C") (class "Default")
      (node (ref "U1") (pin "P$J24") (pinfunction "P0.10/NFC2_P$J24") (pintype "bidirectional"))
    )
    (net (code "5") (name "D+{slash}1.5D") (class "Default")
      (node (ref "D3") (pin "4") (pinfunction "I/O2_2_4") (pintype "bidirectional"))
    )
    (net (code "6") (name "D+{slash}2.7D") (class "Default")
      (node (ref "U1") (pin "P$AD6") (pinfunction "D+_P$AD6") (pintype "bidirectional"))
    )
    (net (code "7") (name "D-{slash}1.5D") (class "Default")
      (node (ref "D3") (pin "6") (pinfunction "I/O1_2_6") (pintype "bidirectional"))
    )
    (net (code "8") (name "D-{slash}2.7D") (class "Default")
      (node (ref "U1") (pin "P$AD4") (pinfunction "D-_P$AD4") (pintype "bidirectional"))
    )
    (net (code "9") (name "DEC1") (class "Default")
      (node (ref "C5") (pin "1") (pinfunction "1_1") (pintype "passive"))
      (node (ref "U1") (pin "P$C1") (pinfunction "DEC1_P$C1") (pintype "power_in"))
    )
    (net (code "10") (name "DEC3") (class "Default")
      (node (ref "C11") (pin "1") (pinfunction "1_1") (pintype "passive"))
      (node (ref "U1") (pin "P$D23") (pinfunction "DEC3_P$D23") (pintype "bidirectional"))
    )
    (net (code "11") (name "DEC4_6") (class "Default")
      (node (ref "C10") (pin "1") (pinfunction "1_1") (pintype "passive"))
      (node (ref "C15") (pin "1") (pinfunction "1_1") (pintype "passive"))
      (node (ref "C16") (pin "1") (pinfunction "1_1") (pintype "passive"))
      (node (ref "L3") (pin "2") (pinfunction "2_2") (pintype "passive"))
      (node (ref "U1") (pin "P$B5") (pinfunction "DEC4_P$B5") (pintype "power_in"))
      (node (ref "U1") (pin "P$E24") (pinfunction "DEC6_P$E24") (pintype "bidirectional"))
    )
    (net (code "12") (name "DN") (class "Default")
      (node (ref "D3") (pin "1") (pinfunction "I/O1_1_1") (pintype "bidirectional"))
      (node (ref "J4") (pin "A7") (pinfunction "DN1_A7") (pintype "bidirectional"))
      (node (ref "J4") (pin "B7") (pinfunction "DN2_B7") (pintype "bidirectional"))
    )
    (net (code "13") (name "DP") (class "Default")
      (node (ref "D3") (pin "3") (pinfunction "I/O2_1_3") (pintype "bidirectional"))
      (node (ref "J4") (pin "A6") (pinfunction "DP1_A6") (pintype "bidirectional"))
      (node (ref "J4") (pin "B6") (pinfunction "DP2_B6") (pintype "bidirectional"))
    )
    (net (code "14") (name "EPD_3V3") (class "Default")
      (node (ref "C1-EP-DR") (pin "1") (pinfunction "1_1") (pintype "passive"))
      (node (ref "DMG2305UX-7") (pin "3") (pinfunction "D_3") (pintype "bidirectional"))
      (node (ref "EPD_C5") (pin "2") (pinfunction "2_2") (pintype "passive"))
      (node (ref "J1") (pin "15") (pinfunction "15_15") (pintype "bidirectional"))
      (node (ref "J1") (pin "16") (pinfunction "16_16") (pintype "bidirectional"))
      (node (ref "L5") (pin "2") (pinfunction "2_2") (pintype "passive"))
    )
    (net (code "15") (name "EPD_BUSY{slash}1.5D") (class "Default")
      (node (ref "J1") (pin "9") (pinfunction "9_9") (pintype "bidirectional"))
    )
    (net (code "16") (name "EPD_BUSY{slash}2.2D") (class "Default")
      (node (ref "U1") (pin "P$AD12") (pinfunction "P0.17_P$AD12") (pintype "bidirectional"))
    )
    (net (code "17") (name "EPD_CS{slash}1.4C") (class "Default")
      (node (ref "J1") (pin "12") (pinfunction "12_12") (pintype "bidirectional"))
    )
    (net (code "18") (name "EPD_CS{slash}2.2D") (class "Default")
      (node (ref "U1") (pin "P$K2") (pinfunction "P0.05/AIN3_P$K2") (pintype "bidirectional"))
    )
    (net (code "19") (name "EPD_DC{slash}1.5D") (class "Default")
      (node (ref "J1") (pin "11") (pinfunction "11_11") (pintype "bidirectional"))
    )
    (net (code "20") (name "EPD_DC{slash}2.2D") (class "Default")
      (node (ref "U1") (pin "P$AD10") (pinfunction "P0.15_P$AD10") (pintype "bidirectional"))
    )
    (net (code "21") (name "EPD_RST{slash}1.5D") (class "Default")
      (node (ref "J1") (pin "10") (pinfunction "10_10") (pintype "bidirectional"))
    )
    (net (code "22") (name "EPD_RST{slash}2.2D") (class "Default")
      (node (ref "U1") (pin "P$AC11") (pinfunction "P0.16_P$AC11") (pintype "bidirectional"))
    )
    (net (code "23") (name "GDR") (class "Default")
      (node (ref "J1") (pin "2") (pinfunction "2_2") (pintype "bidirectional"))
      (node (ref "Q3") (pin "1") (pinfunction "G_1") (pintype "bidirectional"))
      (node (ref "R2_EP_DR") (pin "2") (pinfunction "2_2") (pintype "bidirectional"))
    )
    (net (code "24") (name "GND") (class "Default")
      (node (ref "C1") (pin "2") (pinfunction "2_2") (pintype "passive"))
      (node (ref "C1-EP-DR") (pin "2") (pinfunction "2_2") (pintype "passive"))
      (node (ref "C10") (pin "2") (pinfunction "2_2") (pintype "passive"))
      (node (ref "C11") (pin "2") (pinfunction "2_2") (pintype "passive"))
      (node (ref "C12") (pin "2") (pinfunction "2_2") (pintype "passive"))
      (node (ref "C13") (pin "2") (pinfunction "2_2") (pintype "passive"))
      (node (ref "C14") (pin "2") (pinfunction "2_2") (pintype "passive"))
      (node (ref "C15") (pin "2") (pinfunction "2_2") (pintype "passive"))
      (node (ref "C16") (pin "2") (pinfunction "2_2") (pintype "passive"))
      (node (ref "C17") (pin "1") (pinfunction "1_1") (pintype "passive"))
      (node (ref "C18") (pin "1") (pinfunction "1_1") (pintype "passive"))
      (node (ref "C19") (pin "2") (pinfunction "2_2") (pintype "passive"))
      (node (ref "C2") (pin "2") (pinfunction "2_2") (pintype "passive"))
      (node (ref "C20") (pin "2") (pinfunction "2_2") (pintype "passive"))
      (node (ref "C21") (pin "2") (pinfunction "2_2") (pintype "passive"))
      (node (ref "C22") (pin "2") (pinfunction "2_2") (pintype "passive"))
      (node (ref "C23") (pin "2") (pinfunction "2_2") (pintype "passive"))
      (node (ref "C24") (pin "1") (pinfunction "1_1") (pintype "passive"))
      (node (ref "C25") (pin "2") (pinfunction "2_2") (pintype "passive"))
      (node (ref "C27") (pin "1") (pinfunction "1_1") (pintype "passive"))
      (node (ref "C29") (pin "1") (pinfunction "1_1") (pintype "passive"))
      (node (ref "C3") (pin "2") (pinfunction "2_2") (pintype "passive"))
      (node (ref "C30") (pin "1") (pinfunction "1_1") (pintype "passive"))
      (node (ref "C31") (pin "1") (pinfunction "1_1") (pintype "passive"))
      (node (ref "C32") (pin "1") (pinfunction "1_1") (pintype "passive"))
      (node (ref "C33") (pin "2") (pinfunction "2_2") (pintype "passive"))
      (node (ref "C34") (pin "1") (pinfunction "1_1") (pintype "passive"))
      (node (ref "C37") (pin "1") (pinfunction "1_1") (pintype "passive"))
      (node (ref "C38") (pin "1") (pinfunction "1_1") (pintype "passive"))
      (node (ref "C39") (pin "2") (pinfunction "2_2") (pintype "passive"))
      (node (ref "C4") (pin "2") (pinfunction "2_2") (pintype "passive"))
      (node (ref "C42") (pin "2") (pinfunction "2_2") (pintype "passive"))
      (node (ref "C43") (pin "2") (pinfunction "2_2") (pintype "passive"))
      (node (ref "C5") (pin "2") (pinfunction "2_2") (pintype "passive"))
      (node (ref "C6") (pin "2") (pinfunction "2_2") (pintype "passive"))
      (node (ref "C7") (pin "2") (pinfunction "2_2") (pintype "passive"))
      (node (ref "C8") (pin "2") (pinfunction "2_2") (pintype "passive"))
      (node (ref "C9") (pin "2") (pinfunction "2_2") (pintype "passive"))
      (node (ref "D1") (pin "1") (pinfunction "K_1") (pintype "bidirectional"))
      (node (ref "D3") (pin "2") (pinfunction "GND_2") (pintype "bidirectional"))
      (node (ref "EPD_C1") (pin "2") (pinfunction "2_2") (pintype "passive"))
      (node (ref "EPD_C10") (pin "2") (pinfunction "2_2") (pintype "passive"))
      (node (ref "EPD_C11") (pin "2") (pinfunction "2_2") (pintype "passive"))
      (node (ref "EPD_C12") (pin "2") (pinfunction "2_2") (pintype "passive"))
      (node (ref "EPD_C2") (pin "2") (pinfunction "2_2") (pintype "passive"))
      (node (ref "EPD_C5") (pin "1") (pinfunction "1_1") (pintype "passive"))
      (node (ref "EPD_C6") (pin "2") (pinfunction "2_2") (pintype "passive"))
      (node (ref "EPD_C7") (pin "2") (pinfunction "2_2") (pintype "passive"))
      (node (ref "EPD_C8") (pin "2") (pinfunction "2_2") (pintype "passive"))
      (node (ref "EPD_C9") (pin "2") (pinfunction "2_2") (pintype "passive"))
      (node (ref "IC1") (pin "D2") (pinfunction "GND_D2") (pintype "bidirectional"))
      (node (ref "IC2") (pin "B1") (pinfunction "IN/TRIG_B1") (pintype "bidirectional"))
      (node (ref "IC2") (pin "B3") (pinfunction "GND_B3") (pintype "bidirectional"))
      (node (ref "IC3") (pin "8") (pinfunction "GNDIO_8") (pintype "bidirectional"))
      (node (ref "IC3") (pin "9") (pinfunction "GND_9") (pintype "bidirectional"))
      (node (ref "IC9") (pin "B1") (pinfunction "VSEL_B1") (pintype "bidirectional"))
      (node (ref "IC9") (pin "C1") (pinfunction "AGND_C1") (pintype "bidirectional"))
      (node (ref "IC9") (pin "C2") (pinfunction "PGND_1_C2") (pintype "bidirectional"))
      (node (ref "IC9") (pin "C3") (pinfunction "PGND_2_C3") (pintype "bidirectional"))
      (node (ref "J1") (pin "17") (pinfunction "17_17") (pintype "bidirectional"))
      (node (ref "J1") (pin "8") (pinfunction "8_8") (pintype "bidirectional"))
      (node (ref "J1") (pin "MP1") (pinfunction "MP1_MP1") (pintype "bidirectional"))
      (node (ref "J1") (pin "MP2") (pinfunction "MP2_MP2") (pintype "bidirectional"))
      (node (ref "J2") (pin "3") (pinfunction "3_3") (pintype "bidirectional"))
      (node (ref "J2") (pin "5") (pinfunction "5_5") (pintype "bidirectional"))
      (node (ref "J4") (pin "A12_B1") (pinfunction "GND_A12_B1") (pintype "power_in"))
      (node (ref "J4") (pin "A1_B12") (pinfunction "GND_A1_B12") (pintype "power_in"))
      (node (ref "J4") (pin "SH1") (pinfunction "SHIELD_SH1") (pintype "passive"))
      (node (ref "J4") (pin "SH2") (pinfunction "SHIELD_SH2") (pintype "passive"))
      (node (ref "J4") (pin "SH3") (pinfunction "SHIELD_SH3") (pintype "passive"))
      (node (ref "J4") (pin "SH4") (pinfunction "SHIELD_SH4") (pintype "passive"))
      (node (ref "R1_USB") (pin "1") (pinfunction "1_1") (pintype "bidirectional"))
      (node (ref "R2_EP_DR") (pin "1") (pinfunction "1_1") (pintype "bidirectional"))
      (node (ref "R2_USB") (pin "2") (pinfunction "2_2") (pintype "bidirectional"))
      (node (ref "R3") (pin "1") (pinfunction "1_1") (pintype "bidirectional"))
      (node (ref "R9") (pin "1") (pinfunction "1_1") (pintype "bidirectional"))
      (node (ref "R_TYPE_SEL") (pin "1") (pinfunction "1_1") (pintype "bidirectional"))
      (node (ref "SJ1") (pin "1") (pinfunction "1_1") (pintype "passive"))
      (node (ref "SW_DN") (pin "1") (pinfunction "1_1") (pintype "passive"))
      (node (ref "SW_ENT") (pin "1") (pinfunction "1_1") (pintype "passive"))
      (node (ref "SW_UP") (pin "1") (pinfunction "1_1") (pintype "passive"))
      (node (ref "TP_GND") (pin "TP") (pinfunction "TP_TP") (pintype "input"))
      (node (ref "TP_VBAT_GND") (pin "TP") (pinfunction "TP_TP") (pintype "input"))
      (node (ref "U1") (pin "P$74") (pinfunction "VSS_PAD_P$74") (pintype "bidirectional"))
      (node (ref "U1") (pin "P$75") (pinfunction "VSS_PAD_P$75") (pintype "bidirectional"))
      (node (ref "U1") (pin "P$76") (pinfunction "VSS_PAD_P$76") (pintype "bidirectional"))
      (node (ref "U1") (pin "P$77") (pinfunction "VSS_PAD_P$77") (pintype "bidirectional"))
      (node (ref "U1") (pin "P$78") (pinfunction "VSS_PAD_P$78") (pintype "bidirectional"))
      (node (ref "U1") (pin "P$79") (pinfunction "VSS_PAD_P$79") (pintype "bidirectional"))
      (node (ref "U1") (pin "P$80") (pinfunction "VSS_PAD_P$80") (pintype "bidirectional"))
      (node (ref "U1") (pin "P$81") (pinfunction "VSS_PAD_P$81") (pintype "bidirectional"))
      (node (ref "U1") (pin "P$82") (pinfunction "VSS_PAD_P$82") (pintype "bidirectional"))
      (node (ref "U1") (pin "P$83") (pinfunction "VSS_PAD_P$83") (pintype "bidirectional"))
      (node (ref "U1") (pin "P$84") (pinfunction "VSS_PAD_P$84") (pintype "bidirectional"))
      (node (ref "U1") (pin "P$85") (pinfunction "VSS_PAD_P$85") (pintype "bidirectional"))
      (node (ref "U1") (pin "P$86") (pinfunction "VSS_PAD_P$86") (pintype "bidirectional"))
      (node (ref "U1") (pin "P$87") (pinfunction "VSS_PAD_P$87") (pintype "bidirectional"))
      (node (ref "U1") (pin "P$88") (pinfunction "VSS_PAD_P$88") (pintype "bidirectional"))
      (node (ref "U1") (pin "P$89") (pinfunction "VSS_PAD_P$89") (pintype "bidirectional"))
      (node (ref "U1") (pin "P$90") (pinfunction "VSS_PAD_P$90") (pintype "bidirectional"))
      (node (ref "U1") (pin "P$B7") (pinfunction "VSS_P$B7") (pintype "power_in"))
      (node (ref "U1") (pin "P$F23") (pinfunction "VSS_PA_P$F23") (pintype "bidirectional"))
      (node (ref "U3") (pin "1") (pinfunction "CTG_1") (pintype "power_in"))
      (node (ref "U3") (pin "4") (pinfunction "GND_4") (pintype "power_in"))
      (node (ref "U3") (pin "6") (pinfunction "QSTRT_6") (pintype "input"))
      (node (ref "U3") (pin "9") (pinfunction "EP_9") (pintype "power_in"))
      (node (ref "X1") (pin "2") (pinfunction "2_2") (pintype "passive"))
      (node (ref "X1") (pin "4") (pinfunction "4_4") (pintype "passive"))
    )
    (net (code "25") (name "HAPTIC-EN{slash}1.4C") (class "Default")
      (node (ref "IC2") (pin "A1") (pinfunction "EN_A1") (pintype "bidirectional"))
    )
    (net (code "26") (name "HAPTIC_EN{slash}2.6A") (class "Default")
      (node (ref "U1") (pin "P$U1") (pinfunction "P0.12_P$U1") (pintype "bidirectional"))
    )
    (net (code "27") (name "IMU_INT1") (class "Default")
      (node (ref "IC3") (pin "5") (pinfunction "INT1_5") (pintype "bidirectional"))
      (node (ref "U1") (pin "P$N1") (pinfunction "P0.08_P$N1") (pintype "bidirectional"))
    )
    (net (code "28") (name "IMU_INT2") (class "Default")
      (node (ref "IC3") (pin "6") (pinfunction "INT2_6") (pintype "bidirectional"))
      (node (ref "U1") (pin "P$P2") (pinfunction "P1.08_P$P2") (pintype "bidirectional"))
    )
    (net (code "29") (name "LX1") (class "Default")
      (node (ref "IC9") (pin "B2") (pinfunction "SW1_1_B2") (pintype "bidirectional"))
      (node (ref "IC9") (pin "B3") (pinfunction "SW1_2_B3") (pintype "bidirectional"))
      (node (ref "L7") (pin "1") (pinfunction "1_1") (pintype "bidirectional"))
    )
    (net (code "30") (name "LX2") (class "Default")
      (node (ref "IC9") (pin "D2") (pinfunction "SW2_1_D2") (pintype "bidirectional"))
      (node (ref "IC9") (pin "D3") (pinfunction "SW2_2_D3") (pintype "bidirectional"))
      (node (ref "L7") (pin "2") (pinfunction "2_2") (pintype "bidirectional"))
    )
    (net (code "31") (name "MOSI{slash}1.5B") (class "Default")
      (node (ref "J1") (pin "14") (pinfunction "14_14") (pintype "bidirectional"))
    )
    (net (code "32") (name "MOSI{slash}2.2D") (class "Default")
      (node (ref "U1") (pin "P$B13") (pinfunction "P0.03/AIN1_P$B13") (pintype "bidirectional"))
    )
    (net (code "33") (name "Net-(D1-A)") (class "Default")
      (node (ref "C2-EP-DR") (pin "1") (pinfunction "1_1") (pintype "passive"))
      (node (ref "D1") (pin "2") (pinfunction "A_2") (pintype "bidirectional"))
      (node (ref "D5") (pin "1") (pinfunction "K_1") (pintype "bidirectional"))
    )
    (net (code "34") (name "Net-(D2-A)") (class "Default")
      (node (ref "C2-EP-DR") (pin "2") (pinfunction "2_2") (pintype "passive"))
      (node (ref "D2") (pin "2") (pinfunction "A_2") (pintype "bidirectional"))
      (node (ref "L5") (pin "1") (pinfunction "1_1") (pintype "passive"))
      (node (ref "Q3") (pin "3") (pinfunction "D_3") (pintype "bidirectional"))
    )
    (net (code "35") (name "Net-(EPD_C1-Pad1)") (class "Default")
      (node (ref "EPD_C1") (pin "1") (pinfunction "1_1") (pintype "passive"))
      (node (ref "J1") (pin "5") (pinfunction "5_5") (pintype "bidirectional"))
    )
    (net (code "36") (name "Net-(EPD_C2-Pad1)") (class "Default")
      (node (ref "EPD_C2") (pin "1") (pinfunction "1_1") (pintype "passive"))
      (node (ref "J1") (pin "4") (pinfunction "4_4") (pintype "bidirectional"))
    )
    (net (code "37") (name "Net-(EPD_C6-Pad1)") (class "Default")
      (node (ref "EPD_C6") (pin "1") (pinfunction "1_1") (pintype "passive"))
      (node (ref "J1") (pin "18") (pinfunction "18_18") (pintype "bidirectional"))
    )
    (net (code "38") (name "Net-(EPD_C7-Pad1)") (class "Default")
      (node (ref "EPD_C7") (pin "1") (pinfunction "1_1") (pintype "passive"))
      (node (ref "J1") (pin "19") (pinfunction "19_19") (pintype "bidirectional"))
    )
    (net (code "39") (name "Net-(EPD_C8-Pad1)") (class "Default")
      (node (ref "EPD_C8") (pin "1") (pinfunction "1_1") (pintype "passive"))
      (node (ref "J1") (pin "20") (pinfunction "20_20") (pintype "bidirectional"))
    )
    (net (code "40") (name "Net-(EPD_C9-Pad1)") (class "Default")
      (node (ref "EPD_C9") (pin "1") (pinfunction "1_1") (pintype "passive"))
      (node (ref "J1") (pin "21") (pinfunction "21_21") (pintype "bidirectional"))
    )
    (net (code "41") (name "Net-(EPD_C10-Pad1)") (class "Default")
      (node (ref "EPD_C10") (pin "1") (pinfunction "1_1") (pintype "passive"))
      (node (ref "J1") (pin "22") (pinfunction "22_22") (pintype "bidirectional"))
    )
    (net (code "42") (name "Net-(EPD_C11-Pad1)") (class "Default")
      (node (ref "EPD_C11") (pin "1") (pinfunction "1_1") (pintype "passive"))
      (node (ref "J1") (pin "23") (pinfunction "23_23") (pintype "bidirectional"))
    )
    (net (code "43") (name "Net-(EPD_C12-Pad1)") (class "Default")
      (node (ref "EPD_C12") (pin "1") (pinfunction "1_1") (pintype "passive"))
      (node (ref "J1") (pin "24") (pinfunction "24_24") (pintype "bidirectional"))
    )
    (net (code "44") (name "Net-(IC1-TS{slash}MR)") (class "Default")
      (node (ref "IC1") (pin "D1") (pinfunction "TS/MR_D1") (pintype "bidirectional"))
      (node (ref "R9") (pin "2") (pinfunction "2_2") (pintype "bidirectional"))
    )
    (net (code "45") (name "Net-(IC2-REG)") (class "Default")
      (node (ref "C32") (pin "2") (pinfunction "2_2") (pintype "passive"))
      (node (ref "IC2") (pin "A2") (pinfunction "REG_A2") (pintype "bidirectional"))
    )
    (net (code "46") (name "Net-(IC3-SDO)") (class "Default")
      (node (ref "IC3") (pin "1") (pinfunction "SDO_1") (pintype "bidirectional"))
      (node (ref "R3") (pin "2") (pinfunction "2_2") (pintype "bidirectional"))
    )
    (net (code "47") (name "Net-(IC9-SCL)") (class "Default")
      (node (ref "IC9") (pin "D1") (pinfunction "SCL_D1") (pintype "bidirectional"))
      (node (ref "R4") (pin "2") (pinfunction "2_2") (pintype "bidirectional"))
    )
    (net (code "48") (name "Net-(IC9-SDA)") (class "Default")
      (node (ref "IC9") (pin "E1") (pinfunction "SDA_E1") (pintype "bidirectional"))
      (node (ref "R2") (pin "2") (pinfunction "2_2") (pintype "bidirectional"))
    )
    (net (code "49") (name "Net-(J4-CC1)") (class "Default")
      (node (ref "J4") (pin "A5") (pinfunction "CC1_A5") (pintype "bidirectional"))
      (node (ref "R1_USB") (pin "2") (pinfunction "2_2") (pintype "bidirectional"))
    )
    (net (code "50") (name "Net-(J4-CC2)") (class "Default")
      (node (ref "J4") (pin "B5") (pinfunction "CC2_B5") (pintype "bidirectional"))
      (node (ref "R2_USB") (pin "1") (pinfunction "1_1") (pintype "bidirectional"))
    )
    (net (code "51") (name "Net-(L2-Pad2)") (class "Default")
      (node (ref "L2") (pin "2") (pinfunction "2_2") (pintype "passive"))
      (node (ref "L3") (pin "1") (pinfunction "1_1") (pintype "passive"))
    )
    (net (code "52") (name "Net-(R1_EP_DR-Pad1)") (class "Default")
      (node (ref "R1_EP_DR") (pin "1") (pinfunction "1_1") (pintype "bidirectional"))
      (node (ref "R_TYPE_SEL") (pin "2") (pinfunction "2_2") (pintype "bidirectional"))
      (node (ref "SJ1") (pin "2") (pinfunction "2_2") (pintype "passive"))
    )
    (net (code "53") (name "Net-(U1-ANT)") (class "Default")
      (node (ref "C3") (pin "1") (pinfunction "1_1") (pintype "passive"))
      (node (ref "L1") (pin "1") (pinfunction "1_1") (pintype "passive"))
      (node (ref "U1") (pin "P$H23") (pinfunction "ANT_P$H23") (pintype "bidirectional"))
    )
    (net (code "54") (name "Net-(U1-DCC)") (class "Default")
      (node (ref "L2") (pin "1") (pinfunction "1_1") (pintype "passive"))
      (node (ref "U1") (pin "P$B3") (pinfunction "DCC_P$B3") (pintype "output"))
    )
    (net (code "55") (name "Net-(U1-DEC2)") (class "Default")
      (node (ref "C13") (pin "1") (pinfunction "1_1") (pintype "passive"))
      (node (ref "U1") (pin "P$A18") (pinfunction "DEC2_P$A18") (pintype "bidirectional"))
    )
    (net (code "56") (name "Net-(U1-DEC3V3)") (class "Default")
      (node (ref "C20") (pin "1") (pinfunction "1_1") (pintype "passive"))
      (node (ref "U1") (pin "P$AC5") (pinfunction "DEC3V3_P$AC5") (pintype "bidirectional"))
    )
    (net (code "57") (name "Net-(U1-DEC5)") (class "Default")
      (node (ref "C9") (pin "1") (pinfunction "1_1") (pintype "passive"))
      (node (ref "U1") (pin "P$N24") (pinfunction "DEC5_P$N24") (pintype "bidirectional"))
    )
    (net (code "58") (name "Net-(U1-P0.00{slash}XL1)") (class "Default")
      (node (ref "C17") (pin "2") (pinfunction "2_2") (pintype "passive"))
      (node (ref "U1") (pin "P$D2") (pinfunction "P0.00/XL1_P$D2") (pintype "bidirectional"))
      (node (ref "X2") (pin "1") (pinfunction "1_1") (pintype "passive"))
    )
    (net (code "59") (name "Net-(U1-P0.01{slash}XL2)") (class "Default")
      (node (ref "C18") (pin "2") (pinfunction "2_2") (pintype "passive"))
      (node (ref "U1") (pin "P$F2") (pinfunction "P0.01/XL2_P$F2") (pintype "bidirectional"))
      (node (ref "X2") (pin "2") (pinfunction "2_2") (pintype "passive"))
    )
    (net (code "60") (name "Net-(U1-XC1)") (class "Default")
      (node (ref "C1") (pin "1") (pinfunction "1_1") (pintype "passive"))
      (node (ref "U1") (pin "P$B24") (pinfunction "XC1_P$B24") (pintype "input"))
      (node (ref "X1") (pin "1") (pinfunction "1_1") (pintype "passive"))
    )
    (net (code "61") (name "Net-(U1-XC2)") (class "Default")
      (node (ref "C2") (pin "1") (pinfunction "1_1") (pintype "passive"))
      (node (ref "U1") (pin "P$A23") (pinfunction "XC2_P$A23") (pintype "output"))
      (node (ref "X1") (pin "3") (pinfunction "3_3") (pintype "passive"))
    )
    (net (code "62") (name "OUT+") (class "Default")
      (node (ref "IC2") (pin "A3") (pinfunction "OUT+_A3") (pintype "bidirectional"))
      (node (ref "TP_OP") (pin "TP") (pinfunction "TP_TP") (pintype "input"))
    )
    (net (code "63") (name "OUT-") (class "Default")
      (node (ref "IC2") (pin "C3") (pinfunction "OUT-_C3") (pintype "bidirectional"))
      (node (ref "TP_ON") (pin "TP") (pinfunction "TP_TP") (pintype "input"))
    )
    (net (code "64") (name "P0.04") (class "Default")
      (node (ref "U1") (pin "P$J1") (pinfunction "P0.04/AIN2_P$J1") (pintype "bidirectional"))
    )
    (net (code "65") (name "P0.09") (class "Default")
      (node (ref "U1") (pin "P$L24") (pinfunction "P0.09/NFC1_P$L24") (pintype "bidirectional"))
    )
    (net (code "66") (name "P0.13{slash}1.5D") (class "Default")
      (node (ref "C30") (pin "2") (pinfunction "2_2") (pintype "passive"))
      (node (ref "R5") (pin "1") (pinfunction "1_1") (pintype "bidirectional"))
      (node (ref "SW_UP") (pin "2") (pinfunction "2_2") (pintype "passive"))
    )
    (net (code "67") (name "P0.13{slash}2.6C") (class "Default")
      (node (ref "U1") (pin "P$AD8") (pinfunction "P0.13_P$AD8") (pintype "bidirectional"))
    )
    (net (code "68") (name "P0.14{slash}1.5D") (class "Default")
      (node (ref "C31") (pin "2") (pinfunction "2_2") (pintype "passive"))
      (node (ref "R8") (pin "1") (pinfunction "1_1") (pintype "bidirectional"))
      (node (ref "SW_ENT") (pin "2") (pinfunction "2_2") (pintype "passive"))
    )
    (net (code "69") (name "P0.14{slash}2.7C") (class "Default")
      (node (ref "U1") (pin "P$AC9") (pinfunction "P0.14_P$AC9") (pintype "bidirectional"))
    )
    (net (code "70") (name "P0.19") (class "Default")
      (node (ref "U1") (pin "P$AC15") (pinfunction "P0.19_P$AC15") (pintype "bidirectional"))
    )
    (net (code "71") (name "P0.20") (class "Default")
      (node (ref "U1") (pin "P$AD16") (pinfunction "P0.20_P$AD16") (pintype "bidirectional"))
    )
    (net (code "72") (name "P0.21") (class "Default")
      (node (ref "U1") (pin "P$AC17") (pinfunction "P0.21_P$AC17") (pintype "bidirectional"))
    )
    (net (code "73") (name "P0.22") (class "Default")
      (node (ref "U1") (pin "P$AD18") (pinfunction "P0.22_P$AD18") (pintype "bidirectional"))
    )
    (net (code "74") (name "P0.23") (class "Default")
      (node (ref "U1") (pin "P$AC19") (pinfunction "P0.23_P$AC19") (pintype "bidirectional"))
    )
    (net (code "75") (name "P0.24") (class "Default")
      (node (ref "U1") (pin "P$AD20") (pinfunction "P0.24_P$AD20") (pintype "bidirectional"))
    )
    (net (code "76") (name "P0.25") (class "Default")
      (node (ref "U1") (pin "P$AC21") (pinfunction "P0.25_P$AC21") (pintype "bidirectional"))
    )
    (net (code "77") (name "P0.26") (class "Default")
      (node (ref "U1") (pin "P$G1") (pinfunction "P0.26_P$G1") (pintype "bidirectional"))
    )
    (net (code "78") (name "P0.27") (class "Default")
      (node (ref "U1") (pin "P$H2") (pinfunction "P0.27_P$H2") (pintype "bidirectional"))
    )
    (net (code "79") (name "P0.28") (class "Default")
      (node (ref "U1") (pin "P$B11") (pinfunction "P0.28/AIN4_P$B11") (pintype "bidirectional"))
    )
    (net (code "80") (name "P0.29") (class "Default")
      (node (ref "U1") (pin "P$A10") (pinfunction "P0.29/AIN5_P$A10") (pintype "bidirectional"))
    )
    (net (code "81") (name "P0.30") (class "Default")
      (node (ref "U1") (pin "P$B9") (pinfunction "P0.30/AIN6_P$B9") (pintype "bidirectional"))
    )
    (net (code "82") (name "P0.31") (class "Default")
      (node (ref "U1") (pin "P$A8") (pinfunction "P0.31/AIN7_P$A8") (pintype "bidirectional"))
    )
    (net (code "83") (name "P1.01{slash}1.6C") (class "Default")
      (node (ref "DMG2305UX-7") (pin "1") (pinfunction "G_1") (pintype "bidirectional"))
      (node (ref "R_PWR_EPD") (pin "1") (pinfunction "1_1") (pintype "bidirectional"))
    )
    (net (code "84") (name "P1.01{slash}2.4B") (class "Default")
      (node (ref "U1") (pin "P$Y23") (pinfunction "P1.01_P$Y23") (pintype "bidirectional"))
    )
    (net (code "85") (name "P1.02{slash}1.6C") (class "Default")
      (node (ref "C29") (pin "2") (pinfunction "2_2") (pintype "passive"))
      (node (ref "R7") (pin "1") (pinfunction "1_1") (pintype "bidirectional"))
      (node (ref "SW_DN") (pin "2") (pinfunction "2_2") (pintype "passive"))
    )
    (net (code "86") (name "P1.02{slash}2.8C") (class "Default")
      (node (ref "U1") (pin "P$W24") (pinfunction "P1.02_P$W24") (pintype "bidirectional"))
    )
    (net (code "87") (name "P1.03") (class "Default")
      (node (ref "U1") (pin "P$V23") (pinfunction "P1.03_P$V23") (pintype "bidirectional"))
    )
    (net (code "88") (name "P1.04") (class "Default")
      (node (ref "U1") (pin "P$U24") (pinfunction "P1.04_P$U24") (pintype "bidirectional"))
    )
    (net (code "89") (name "P1.05") (class "Default")
      (node (ref "U1") (pin "P$T23") (pinfunction "P1.05_P$T23") (pintype "bidirectional"))
    )
    (net (code "90") (name "P1.06") (class "Default")
      (node (ref "U1") (pin "P$R24") (pinfunction "P1.06_P$R24") (pintype "bidirectional"))
    )
    (net (code "91") (name "P1.07") (class "Default")
      (node (ref "U1") (pin "P$P23") (pinfunction "P1.07_P$P23") (pintype "bidirectional"))
    )
    (net (code "92") (name "P1.09") (class "Default")
      (node (ref "U1") (pin "P$R1") (pinfunction "P1.09_P$R1") (pintype "bidirectional"))
    )
    (net (code "93") (name "P1.10") (class "Default")
      (node (ref "U1") (pin "P$A20") (pinfunction "P1.10_P$A20") (pintype "bidirectional"))
    )
    (net (code "94") (name "P1.11") (class "Default")
      (node (ref "U1") (pin "P$B19") (pinfunction "P1.11_P$B19") (pintype "bidirectional"))
    )
    (net (code "95") (name "P1.12") (class "Default")
      (node (ref "U1") (pin "P$B17") (pinfunction "P1.12_P$B17") (pintype "bidirectional"))
    )
    (net (code "96") (name "P1.13") (class "Default")
      (node (ref "U1") (pin "P$A16") (pinfunction "P1.13_P$A16") (pintype "bidirectional"))
    )
    (net (code "97") (name "P1.14") (class "Default")
      (node (ref "U1") (pin "P$B15") (pinfunction "P1.14_P$B15") (pintype "bidirectional"))
    )
    (net (code "98") (name "P1.15") (class "Default")
      (node (ref "U1") (pin "P$A14") (pinfunction "P1.15_P$A14") (pintype "bidirectional"))
    )
    (net (code "99") (name "PMIC_INT") (class "Default")
      (node (ref "IC1") (pin "A1") (pinfunction "~{INT}_A1") (pintype "bidirectional"))
      (node (ref "U1") (pin "P$T2") (pinfunction "P0.11_P$T2") (pintype "bidirectional"))
    )
    (net (code "100") (name "PREVGH") (class "Default")
      (node (ref "D2") (pin "1") (pinfunction "K_1") (pintype "bidirectional"))
    )
    (net (code "101") (name "PREVGL") (class "Default")
      (node (ref "D5") (pin "2") (pinfunction "A_2") (pintype "bidirectional"))
    )
    (net (code "102") (name "RESE") (class "Default")
      (node (ref "J1") (pin "3") (pinfunction "3_3") (pintype "bidirectional"))
      (node (ref "Q3") (pin "2") (pinfunction "S_2") (pintype "bidirectional"))
      (node (ref "R1_EP_DR") (pin "2") (pinfunction "2_2") (pintype "bidirectional"))
    )
    (net (code "103") (name "RESET") (class "Default")
      (node (ref "J2") (pin "6") (pinfunction "6_6") (pintype "bidirectional"))
      (node (ref "TP_RESET") (pin "TP") (pinfunction "TP_TP") (pintype "input"))
      (node (ref "U1") (pin "P$AC13") (pinfunction "P0.18/RESET_P$AC13") (pintype "bidirectional"))
    )
    (net (code "104") (name "RF") (class "Default")
      (node (ref "ANT1") (pin "1") (pinfunction "FEED_1") (pintype "input"))
      (node (ref "C22") (pin "1") (pinfunction "1_1") (pintype "passive"))
      (node (ref "C4") (pin "1") (pinfunction "1_1") (pintype "passive"))
      (node (ref "L1") (pin "2") (pinfunction "2_2") (pintype "passive"))
    )
    (net (code "105") (name "SCK{slash}1.5B") (class "Default")
      (node (ref "J1") (pin "13") (pinfunction "13_13") (pintype "bidirectional"))
    )
    (net (code "106") (name "SCK{slash}2.2D") (class "Default")
      (node (ref "U1") (pin "P$A12") (pinfunction "P0.02/AIN0_P$A12") (pintype "bidirectional"))
    )
    (net (code "107") (name "SCL{slash}1.4C") (class "Default")
      (node (ref "IC2") (pin "C1") (pinfunction "SCL_C1") (pintype "bidirectional"))
      (node (ref "U3") (pin "7") (pinfunction "SCL_7") (pintype "input"))
    )
    (net (code "108") (name "SCL{slash}2.4C") (class "Default")
      (node (ref "IC1") (pin "B1") (pinfunction "SCL_B1") (pintype "bidirectional"))
      (node (ref "IC3") (pin "12") (pinfunction "SCX_12") (pintype "bidirectional"))
      (node (ref "R17") (pin "2") (pinfunction "2_2") (pintype "bidirectional"))
      (node (ref "R4") (pin "1") (pinfunction "1_1") (pintype "bidirectional"))
      (node (ref "TP_SCL") (pin "TP") (pinfunction "TP_TP") (pintype "input"))
      (node (ref "U1") (pin "P$M2") (pinfunction "P0.07_P$M2") (pintype "bidirectional"))
    )
    (net (code "109") (name "SDA{slash}1.4C") (class "Default")
      (node (ref "IC2") (pin "B2") (pinfunction "SDA_B2") (pintype "bidirectional"))
      (node (ref "U3") (pin "8") (pinfunction "SDA_8") (pintype "bidirectional"))
    )
    (net (code "110") (name "SDA{slash}2.4C") (class "Default")
      (node (ref "IC1") (pin "C1") (pinfunction "SDA_C1") (pintype "bidirectional"))
      (node (ref "IC3") (pin "2") (pinfunction "SDX_2") (pintype "bidirectional"))
      (node (ref "R18") (pin "2") (pinfunction "2_2") (pintype "bidirectional"))
      (node (ref "R2") (pin "1") (pinfunction "1_1") (pintype "bidirectional"))
      (node (ref "TP_SDA") (pin "TP") (pinfunction "TP_TP") (pintype "input"))
      (node (ref "U1") (pin "P$L1") (pinfunction "P0.06_P$L1") (pintype "bidirectional"))
    )
    (net (code "111") (name "SWDCLK") (class "Default")
      (node (ref "J2") (pin "4") (pinfunction "4_4") (pintype "bidirectional"))
      (node (ref "TP_SWDCLK") (pin "TP") (pinfunction "TP_TP") (pintype "input"))
      (node (ref "U1") (pin "P$AA24") (pinfunction "SWDCLK_P$AA24") (pintype "input"))
    )
    (net (code "112") (name "SWDIO") (class "Default")
      (node (ref "J2") (pin "2") (pinfunction "2_2") (pintype "bidirectional"))
      (node (ref "TP_SWIO") (pin "TP") (pinfunction "TP_TP") (pintype "input"))
      (node (ref "U1") (pin "P$AC24") (pinfunction "SWDIO_P$AC24") (pintype "bidirectional"))
    )
    (net (code "113") (name "SWO") (class "Default")
      (node (ref "TP_SWO") (pin "TP") (pinfunction "TP_TP") (pintype "input"))
      (node (ref "U1") (pin "P$AD22") (pinfunction "P1.00_P$AD22") (pintype "bidirectional"))
    )
    (net (code "114") (name "VBAT{slash}1.2A") (class "Default")
      (node (ref "C27") (pin "2") (pinfunction "2_2") (pintype "passive"))
      (node (ref "TP_VBAT") (pin "TP") (pinfunction "TP_TP") (pintype "input"))
      (node (ref "U3") (pin "2") (pinfunction "CELL_2") (pintype "power_in"))
      (node (ref "U3") (pin "3") (pinfunction "VDD_3") (pintype "power_in"))
    )
    (net (code "115") (name "VBAT{slash}2.5C") (class "Default")
      (node (ref "C37") (pin "2") (pinfunction "2_2") (pintype "passive"))
      (node (ref "IC1") (pin "C2") (pinfunction "BAT_C2") (pintype "bidirectional"))
    )
    (net (code "116") (name "VBUS{slash}1.5D") (class "Default")
      (node (ref "C42") (pin "1") (pinfunction "1_1") (pintype "passive"))
      (node (ref "C43") (pin "1") (pinfunction "1_1") (pintype "passive"))
      (node (ref "D3") (pin "5") (pinfunction "VBUS_5") (pintype "bidirectional"))
      (node (ref "J4") (pin "A4_B9") (pinfunction "VBUS_A4_B9") (pintype "power_in"))
      (node (ref "J4") (pin "A9_B4") (pinfunction "VBUS_A9_B4") (pintype "power_in"))
    )
    (net (code "117") (name "VBUS{slash}2.6D") (class "Default")
      (node (ref "C21") (pin "1") (pinfunction "1_1") (pintype "passive"))
      (node (ref "C38") (pin "2") (pinfunction "2_2") (pintype "passive"))
      (node (ref "IC1") (pin "A2") (pinfunction "IN_A2") (pintype "bidirectional"))
      (node (ref "U1") (pin "P$AD2") (pinfunction "VBUS_P$AD2") (pintype "power_in"))
    )
    (net (code "118") (name "VREG") (class "Default")
      (node (ref "C23") (pin "1") (pinfunction "1_1") (pintype "passive"))
      (node (ref "C24") (pin "2") (pinfunction "2_2") (pintype "passive"))
      (node (ref "C39") (pin "1") (pinfunction "1_1") (pintype "passive"))
      (node (ref "IC1") (pin "B2") (pinfunction "SYS_B2") (pintype "bidirectional"))
      (node (ref "IC9") (pin "A1") (pinfunction "EN_A1") (pintype "bidirectional"))
      (node (ref "IC9") (pin "A2") (pinfunction "VIN_1_A2") (pintype "bidirectional"))
      (node (ref "IC9") (pin "A3") (pinfunction "VIN_2_A3") (pintype "bidirectional"))
      (node (ref "TP_VREG") (pin "TP") (pinfunction "TP_TP") (pintype "input"))
    )
    (net (code "119") (name "unconnected-(ANT1-NC-Pad2)") (class "Default")
      (node (ref "ANT1") (pin "2") (pinfunction "NC_2") (pintype "no_connect"))
    )
    (net (code "120") (name "unconnected-(IC3-ASCL-Pad11)") (class "Default")
      (node (ref "IC3") (pin "11") (pinfunction "ASCL_11") (pintype "bidirectional"))
    )
    (net (code "121") (name "unconnected-(IC3-ASDA-Pad4)") (class "Default")
      (node (ref "IC3") (pin "4") (pinfunction "ASDA_4") (pintype "bidirectional"))
    )
    (net (code "122") (name "unconnected-(J1-Pad1)") (class "Default")
      (node (ref "J1") (pin "1") (pinfunction "1_1") (pintype "bidirectional"))
    )
    (net (code "123") (name "unconnected-(J1-Pad6)") (class "Default")
      (node (ref "J1") (pin "6") (pinfunction "6_6") (pintype "bidirectional"))
    )
    (net (code "124") (name "unconnected-(J1-Pad7)") (class "Default")
      (node (ref "J1") (pin "7") (pinfunction "7_7") (pintype "bidirectional"))
    )
    (net (code "125") (name "unconnected-(J4-SBU1-PadA8)") (class "Default")
      (node (ref "J4") (pin "A8") (pinfunction "SBU1_A8") (pintype "bidirectional"))
    )
    (net (code "126") (name "unconnected-(J4-SBU2-PadB8)") (class "Default")
      (node (ref "J4") (pin "B8") (pinfunction "SBU2_B8") (pintype "bidirectional"))
    )
    (net (code "127") (name "unconnected-(U1-DCCH-PadP$AB2)") (class "Default")
      (node (ref "U1") (pin "P$AB2") (pinfunction "DCCH_P$AB2") (pintype "bidirectional"))
    )
  )
)
